# pam-control-module-v0.net
KiCad netlist of a schematic drawn in EAGLE
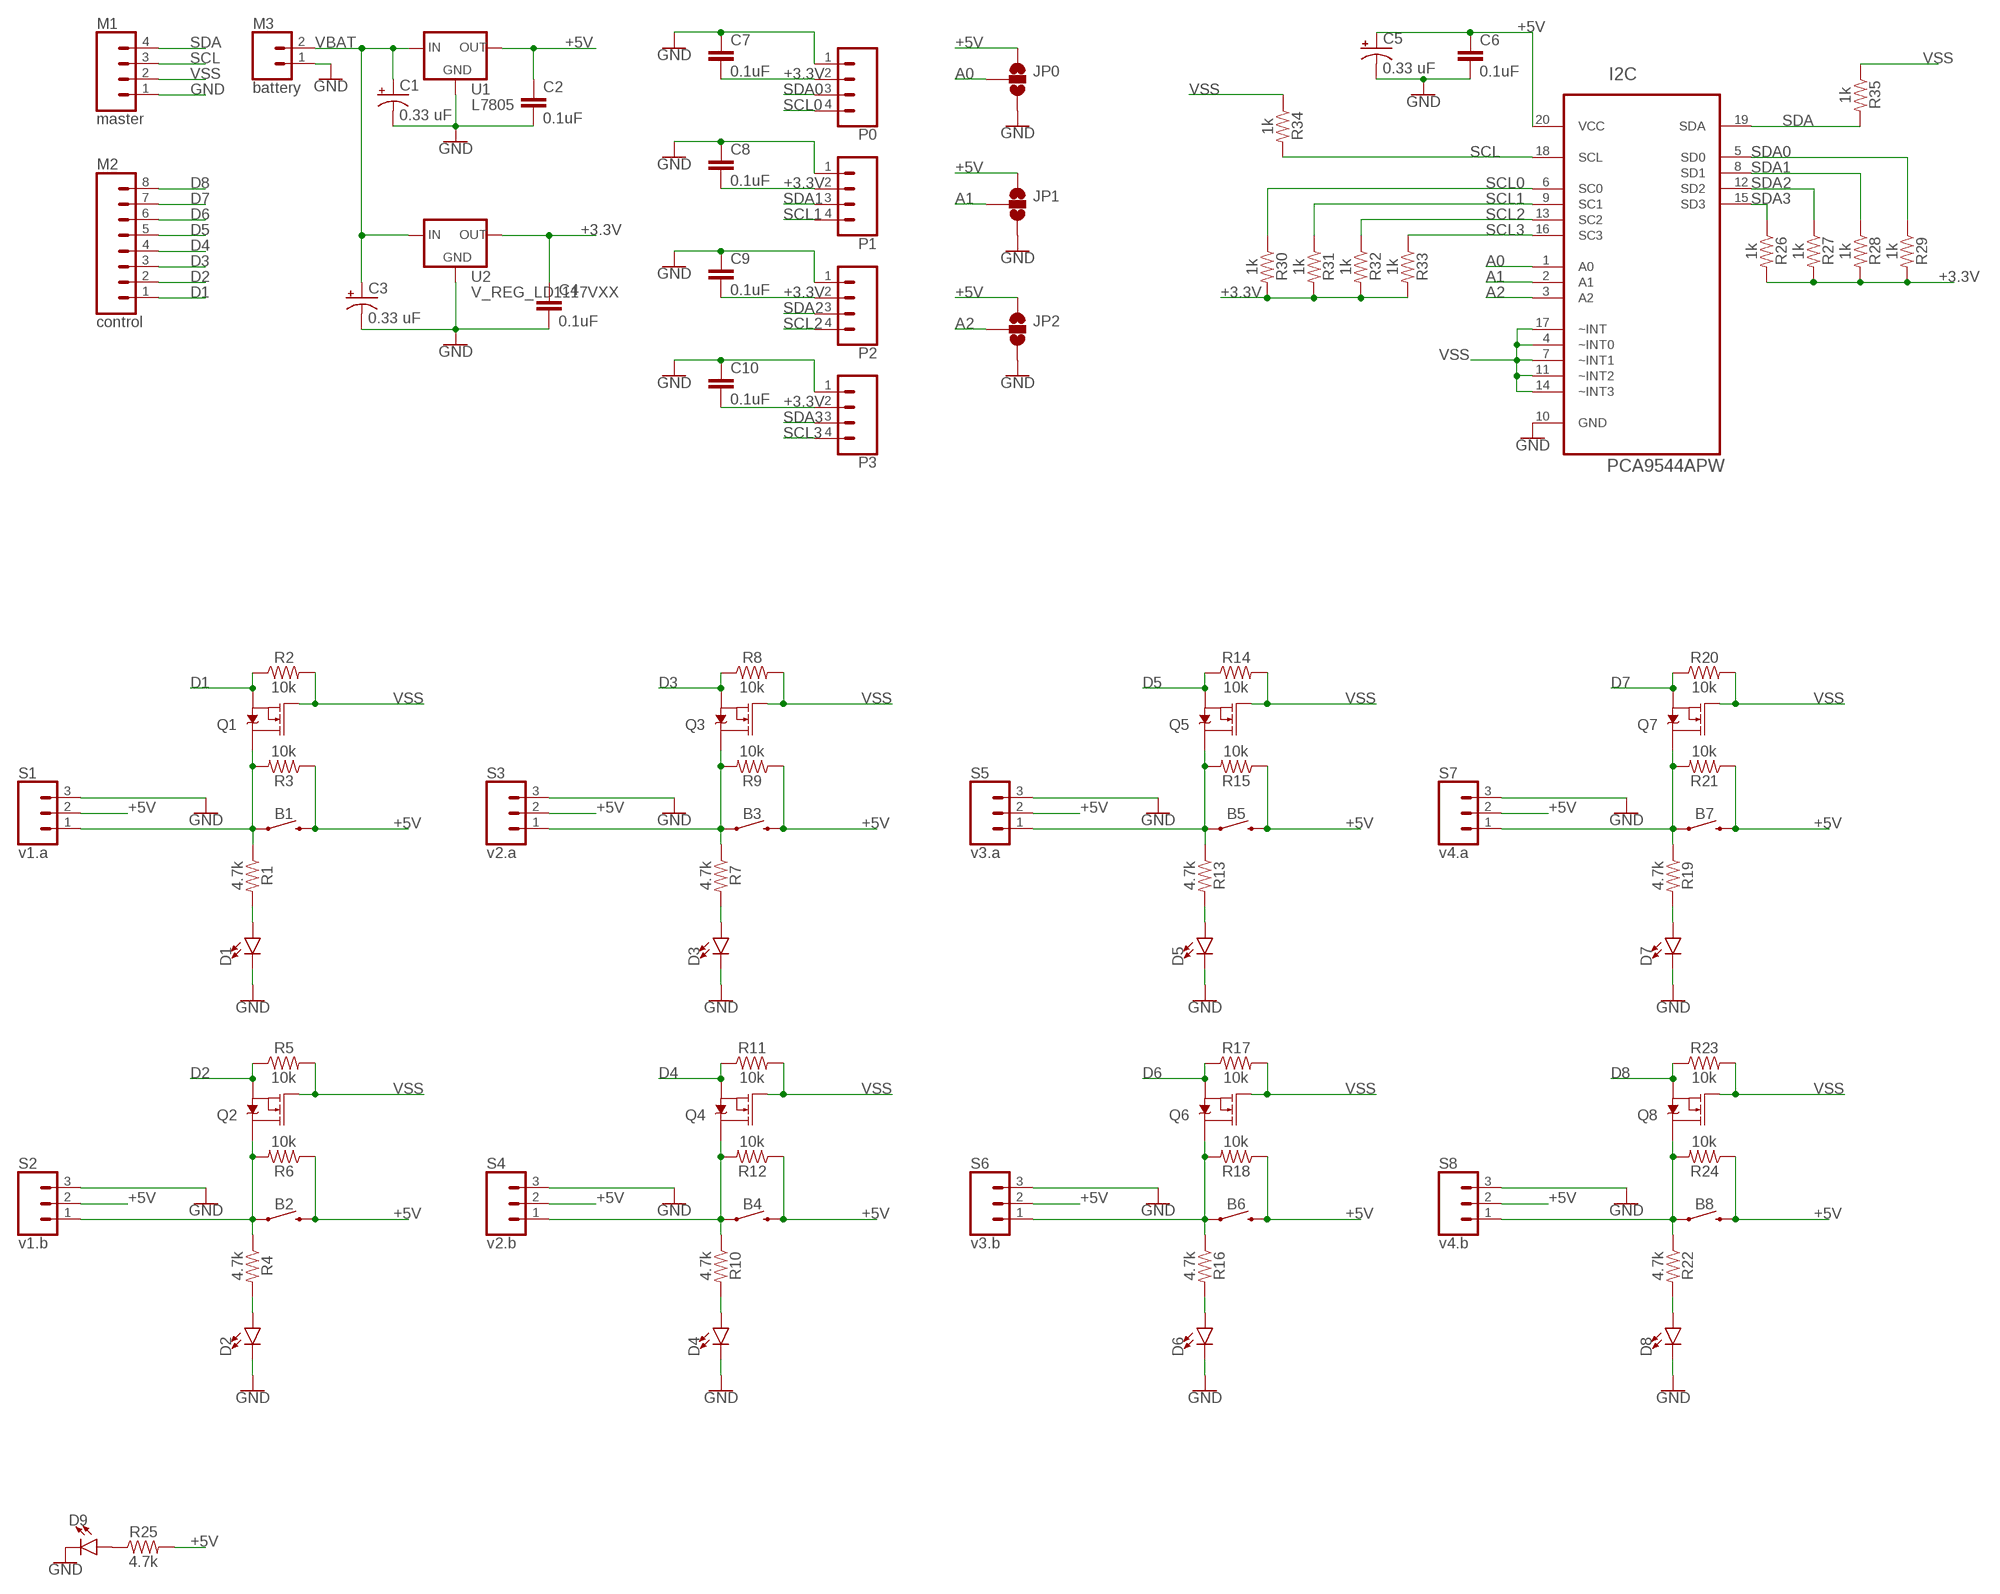
[diagram p0: schematic, sheet 1]

(export (version "E")
  (design (tool "Eeschema 10.0.6"))
  (components
    (comp (ref "B1")
      (value "MOMENTARY-SWITCH-SPST-PTH-6.0MM")
      (footprint "eagle-import:TACTILE_SWITCH_PTH_6.0MM")
      (libsource (lib "eagle-import") (part "MOMENTARY-SWITCH-SPST-PTH-6.0MM"))
    )
    (comp (ref "B2")
      (value "MOMENTARY-SWITCH-SPST-PTH-6.0MM")
      (footprint "eagle-import:TACTILE_SWITCH_PTH_6.0MM")
      (libsource (lib "eagle-import") (part "MOMENTARY-SWITCH-SPST-PTH-6.0MM"))
    )
    (comp (ref "B3")
      (value "MOMENTARY-SWITCH-SPST-PTH-6.0MM")
      (footprint "eagle-import:TACTILE_SWITCH_PTH_6.0MM")
      (libsource (lib "eagle-import") (part "MOMENTARY-SWITCH-SPST-PTH-6.0MM"))
    )
    (comp (ref "B4")
      (value "MOMENTARY-SWITCH-SPST-PTH-6.0MM")
      (footprint "eagle-import:TACTILE_SWITCH_PTH_6.0MM")
      (libsource (lib "eagle-import") (part "MOMENTARY-SWITCH-SPST-PTH-6.0MM"))
    )
    (comp (ref "B5")
      (value "MOMENTARY-SWITCH-SPST-PTH-6.0MM")
      (footprint "eagle-import:TACTILE_SWITCH_PTH_6.0MM")
      (libsource (lib "eagle-import") (part "MOMENTARY-SWITCH-SPST-PTH-6.0MM"))
    )
    (comp (ref "B6")
      (value "MOMENTARY-SWITCH-SPST-PTH-6.0MM")
      (footprint "eagle-import:TACTILE_SWITCH_PTH_6.0MM")
      (libsource (lib "eagle-import") (part "MOMENTARY-SWITCH-SPST-PTH-6.0MM"))
    )
    (comp (ref "B7")
      (value "MOMENTARY-SWITCH-SPST-PTH-6.0MM")
      (footprint "eagle-import:TACTILE_SWITCH_PTH_6.0MM")
      (libsource (lib "eagle-import") (part "MOMENTARY-SWITCH-SPST-PTH-6.0MM"))
    )
    (comp (ref "B8")
      (value "MOMENTARY-SWITCH-SPST-PTH-6.0MM")
      (footprint "eagle-import:TACTILE_SWITCH_PTH_6.0MM")
      (libsource (lib "eagle-import") (part "MOMENTARY-SWITCH-SPST-PTH-6.0MM"))
    )
    (comp (ref "C1")
      (value "0.33 uF")
      (footprint "eagle-import:E2-5")
      (libsource (lib "eagle-import") (part "CPOL-USE2-5"))
    )
    (comp (ref "C2")
      (value "0.1uF")
      (footprint "eagle-import:CAP-PTH-SMALL-KIT")
      (libsource (lib "eagle-import") (part "0.1UF-KIT-EZ-50V-20%"))
    )
    (comp (ref "C3")
      (value "0.33 uF")
      (footprint "eagle-import:E2-5")
      (libsource (lib "eagle-import") (part "CPOL-USE2-5"))
    )
    (comp (ref "C4")
      (value "0.1uF")
      (footprint "eagle-import:CAP-PTH-SMALL-KIT")
      (libsource (lib "eagle-import") (part "0.1UF-KIT-EZ-50V-20%"))
    )
    (comp (ref "C5")
      (value "0.33 uF")
      (footprint "eagle-import:E2-5")
      (libsource (lib "eagle-import") (part "CPOL-USE2-5"))
    )
    (comp (ref "C6")
      (value "0.1uF")
      (footprint "eagle-import:CAP-PTH-SMALL-KIT")
      (libsource (lib "eagle-import") (part "0.1UF-KIT-EZ-50V-20%"))
    )
    (comp (ref "C7")
      (value "0.1uF")
      (footprint "eagle-import:CAP-PTH-SMALL-KIT")
      (libsource (lib "eagle-import") (part "0.1UF-KIT-EZ-50V-20%"))
    )
    (comp (ref "C8")
      (value "0.1uF")
      (footprint "eagle-import:CAP-PTH-SMALL-KIT")
      (libsource (lib "eagle-import") (part "0.1UF-KIT-EZ-50V-20%"))
    )
    (comp (ref "C9")
      (value "0.1uF")
      (footprint "eagle-import:CAP-PTH-SMALL-KIT")
      (libsource (lib "eagle-import") (part "0.1UF-KIT-EZ-50V-20%"))
    )
    (comp (ref "C10")
      (value "0.1uF")
      (footprint "eagle-import:CAP-PTH-SMALL-KIT")
      (libsource (lib "eagle-import") (part "0.1UF-KIT-EZ-50V-20%"))
    )
    (comp (ref "D1")
      (value "LED3MM")
      (footprint "eagle-import:LED_3MM")
      (libsource (lib "eagle-import") (part "LED3MM"))
    )
    (comp (ref "D2")
      (value "LED3MM")
      (footprint "eagle-import:LED_3MM")
      (libsource (lib "eagle-import") (part "LED3MM"))
    )
    (comp (ref "D3")
      (value "LED3MM")
      (footprint "eagle-import:LED_3MM")
      (libsource (lib "eagle-import") (part "LED3MM"))
    )
    (comp (ref "D4")
      (value "LED3MM")
      (footprint "eagle-import:LED_3MM")
      (libsource (lib "eagle-import") (part "LED3MM"))
    )
    (comp (ref "D5")
      (value "LED3MM")
      (footprint "eagle-import:LED_3MM")
      (libsource (lib "eagle-import") (part "LED3MM"))
    )
    (comp (ref "D6")
      (value "LED3MM")
      (footprint "eagle-import:LED_3MM")
      (libsource (lib "eagle-import") (part "LED3MM"))
    )
    (comp (ref "D7")
      (value "LED3MM")
      (footprint "eagle-import:LED_3MM")
      (libsource (lib "eagle-import") (part "LED3MM"))
    )
    (comp (ref "D8")
      (value "LED3MM")
      (footprint "eagle-import:LED_3MM")
      (libsource (lib "eagle-import") (part "LED3MM"))
    )
    (comp (ref "D9")
      (value "LED3MM")
      (footprint "eagle-import:LED_3MM")
      (libsource (lib "eagle-import") (part "LED3MM"))
    )
    (comp (ref "I2C")
      (value "PCA9544APW")
      (footprint "eagle-import:SOP65P640X120-20N")
      (fields (field (name "MF") "Texas Instruments"))
      (libsource (lib "eagle-import") (part "PCA9544APW"))
    )
    (comp (ref "JP0")
      (value "JUMPER-SMT_3_NO_SILK")
      (footprint "eagle-import:SMT-JUMPER_3_NO_SILK")
      (libsource (lib "eagle-import") (part "JUMPER-SMT_3_NO_SILK"))
    )
    (comp (ref "JP1")
      (value "JUMPER-SMT_3_NO_SILK")
      (footprint "eagle-import:SMT-JUMPER_3_NO_SILK")
      (libsource (lib "eagle-import") (part "JUMPER-SMT_3_NO_SILK"))
    )
    (comp (ref "JP2")
      (value "JUMPER-SMT_3_NO_SILK")
      (footprint "eagle-import:SMT-JUMPER_3_NO_SILK")
      (libsource (lib "eagle-import") (part "JUMPER-SMT_3_NO_SILK"))
    )
    (comp (ref "M1")
      (value "master")
      (footprint "eagle-import:1X04")
      (libsource (lib "eagle-import") (part "CONN_04"))
    )
    (comp (ref "M2")
      (value "control")
      (footprint "eagle-import:1X08")
      (libsource (lib "eagle-import") (part "CONN_08{dblquote}"))
    )
    (comp (ref "M3")
      (value "battery")
      (footprint "eagle-import:1X02")
      (libsource (lib "eagle-import") (part "CONN_02"))
    )
    (comp (ref "P0")
      (value "CONN_04")
      (footprint "eagle-import:1X04")
      (libsource (lib "eagle-import") (part "CONN_04"))
    )
    (comp (ref "P1")
      (value "CONN_04")
      (footprint "eagle-import:1X04")
      (libsource (lib "eagle-import") (part "CONN_04"))
    )
    (comp (ref "P2")
      (value "CONN_04")
      (footprint "eagle-import:1X04")
      (libsource (lib "eagle-import") (part "CONN_04"))
    )
    (comp (ref "P3")
      (value "CONN_04")
      (footprint "eagle-import:1X04")
      (libsource (lib "eagle-import") (part "CONN_04"))
    )
    (comp (ref "Q1")
      (value "MOSFET-NCH-BSS138")
      (footprint "eagle-import:SOT23-3")
      (libsource (lib "eagle-import") (part "MOSFET-NCH-BSS138"))
    )
    (comp (ref "Q2")
      (value "MOSFET-NCH-BSS138")
      (footprint "eagle-import:SOT23-3")
      (libsource (lib "eagle-import") (part "MOSFET-NCH-BSS138"))
    )
    (comp (ref "Q3")
      (value "MOSFET-NCH-BSS138")
      (footprint "eagle-import:SOT23-3")
      (libsource (lib "eagle-import") (part "MOSFET-NCH-BSS138"))
    )
    (comp (ref "Q4")
      (value "MOSFET-NCH-BSS138")
      (footprint "eagle-import:SOT23-3")
      (libsource (lib "eagle-import") (part "MOSFET-NCH-BSS138"))
    )
    (comp (ref "Q5")
      (value "MOSFET-NCH-BSS138")
      (footprint "eagle-import:SOT23-3")
      (libsource (lib "eagle-import") (part "MOSFET-NCH-BSS138"))
    )
    (comp (ref "Q6")
      (value "MOSFET-NCH-BSS138")
      (footprint "eagle-import:SOT23-3")
      (libsource (lib "eagle-import") (part "MOSFET-NCH-BSS138"))
    )
    (comp (ref "Q7")
      (value "MOSFET-NCH-BSS138")
      (footprint "eagle-import:SOT23-3")
      (libsource (lib "eagle-import") (part "MOSFET-NCH-BSS138"))
    )
    (comp (ref "Q8")
      (value "MOSFET-NCH-BSS138")
      (footprint "eagle-import:SOT23-3")
      (libsource (lib "eagle-import") (part "MOSFET-NCH-BSS138"))
    )
    (comp (ref "R1")
      (value "4.7k")
      (footprint "eagle-import:AXIAL-0.3")
      (libsource (lib "eagle-import") (part "1KOHM-HORIZ-1/4W-1%"))
    )
    (comp (ref "R2")
      (value "10k")
      (footprint "eagle-import:AXIAL-0.3")
      (libsource (lib "eagle-import") (part "1KOHM-HORIZ-1/4W-1%"))
    )
    (comp (ref "R3")
      (value "10k")
      (footprint "eagle-import:AXIAL-0.3")
      (libsource (lib "eagle-import") (part "1KOHM-HORIZ-1/4W-1%"))
    )
    (comp (ref "R4")
      (value "4.7k")
      (footprint "eagle-import:AXIAL-0.3")
      (libsource (lib "eagle-import") (part "1KOHM-HORIZ-1/4W-1%"))
    )
    (comp (ref "R5")
      (value "10k")
      (footprint "eagle-import:AXIAL-0.3")
      (libsource (lib "eagle-import") (part "1KOHM-HORIZ-1/4W-1%"))
    )
    (comp (ref "R6")
      (value "10k")
      (footprint "eagle-import:AXIAL-0.3")
      (libsource (lib "eagle-import") (part "1KOHM-HORIZ-1/4W-1%"))
    )
    (comp (ref "R7")
      (value "4.7k")
      (footprint "eagle-import:AXIAL-0.3")
      (libsource (lib "eagle-import") (part "1KOHM-HORIZ-1/4W-1%"))
    )
    (comp (ref "R8")
      (value "10k")
      (footprint "eagle-import:AXIAL-0.3")
      (libsource (lib "eagle-import") (part "1KOHM-HORIZ-1/4W-1%"))
    )
    (comp (ref "R9")
      (value "10k")
      (footprint "eagle-import:AXIAL-0.3")
      (libsource (lib "eagle-import") (part "1KOHM-HORIZ-1/4W-1%"))
    )
    (comp (ref "R10")
      (value "4.7k")
      (footprint "eagle-import:AXIAL-0.3")
      (libsource (lib "eagle-import") (part "1KOHM-HORIZ-1/4W-1%"))
    )
    (comp (ref "R11")
      (value "10k")
      (footprint "eagle-import:AXIAL-0.3")
      (libsource (lib "eagle-import") (part "1KOHM-HORIZ-1/4W-1%"))
    )
    (comp (ref "R12")
      (value "10k")
      (footprint "eagle-import:AXIAL-0.3")
      (libsource (lib "eagle-import") (part "1KOHM-HORIZ-1/4W-1%"))
    )
    (comp (ref "R13")
      (value "4.7k")
      (footprint "eagle-import:AXIAL-0.3")
      (libsource (lib "eagle-import") (part "1KOHM-HORIZ-1/4W-1%"))
    )
    (comp (ref "R14")
      (value "10k")
      (footprint "eagle-import:AXIAL-0.3")
      (libsource (lib "eagle-import") (part "1KOHM-HORIZ-1/4W-1%"))
    )
    (comp (ref "R15")
      (value "10k")
      (footprint "eagle-import:AXIAL-0.3")
      (libsource (lib "eagle-import") (part "1KOHM-HORIZ-1/4W-1%"))
    )
    (comp (ref "R16")
      (value "4.7k")
      (footprint "eagle-import:AXIAL-0.3")
      (libsource (lib "eagle-import") (part "1KOHM-HORIZ-1/4W-1%"))
    )
    (comp (ref "R17")
      (value "10k")
      (footprint "eagle-import:AXIAL-0.3")
      (libsource (lib "eagle-import") (part "1KOHM-HORIZ-1/4W-1%"))
    )
    (comp (ref "R18")
      (value "10k")
      (footprint "eagle-import:AXIAL-0.3")
      (libsource (lib "eagle-import") (part "1KOHM-HORIZ-1/4W-1%"))
    )
    (comp (ref "R19")
      (value "4.7k")
      (footprint "eagle-import:AXIAL-0.3")
      (libsource (lib "eagle-import") (part "1KOHM-HORIZ-1/4W-1%"))
    )
    (comp (ref "R20")
      (value "10k")
      (footprint "eagle-import:AXIAL-0.3")
      (libsource (lib "eagle-import") (part "1KOHM-HORIZ-1/4W-1%"))
    )
    (comp (ref "R21")
      (value "10k")
      (footprint "eagle-import:AXIAL-0.3")
      (libsource (lib "eagle-import") (part "1KOHM-HORIZ-1/4W-1%"))
    )
    (comp (ref "R22")
      (value "4.7k")
      (footprint "eagle-import:AXIAL-0.3")
      (libsource (lib "eagle-import") (part "1KOHM-HORIZ-1/4W-1%"))
    )
    (comp (ref "R23")
      (value "10k")
      (footprint "eagle-import:AXIAL-0.3")
      (libsource (lib "eagle-import") (part "1KOHM-HORIZ-1/4W-1%"))
    )
    (comp (ref "R24")
      (value "10k")
      (footprint "eagle-import:AXIAL-0.3")
      (libsource (lib "eagle-import") (part "1KOHM-HORIZ-1/4W-1%"))
    )
    (comp (ref "R25")
      (value "4.7k")
      (footprint "eagle-import:AXIAL-0.3")
      (libsource (lib "eagle-import") (part "1KOHM-HORIZ-1/4W-1%"))
    )
    (comp (ref "R26")
      (value "1k")
      (footprint "eagle-import:AXIAL-0.3")
      (libsource (lib "eagle-import") (part "1KOHM-HORIZ-1/4W-1%"))
    )
    (comp (ref "R27")
      (value "1k")
      (footprint "eagle-import:AXIAL-0.3")
      (libsource (lib "eagle-import") (part "1KOHM-HORIZ-1/4W-1%"))
    )
    (comp (ref "R28")
      (value "1k")
      (footprint "eagle-import:AXIAL-0.3")
      (libsource (lib "eagle-import") (part "1KOHM-HORIZ-1/4W-1%"))
    )
    (comp (ref "R29")
      (value "1k")
      (footprint "eagle-import:AXIAL-0.3")
      (libsource (lib "eagle-import") (part "1KOHM-HORIZ-1/4W-1%"))
    )
    (comp (ref "R30")
      (value "1k")
      (footprint "eagle-import:AXIAL-0.3")
      (libsource (lib "eagle-import") (part "1KOHM-HORIZ-1/4W-1%"))
    )
    (comp (ref "R31")
      (value "1k")
      (footprint "eagle-import:AXIAL-0.3")
      (libsource (lib "eagle-import") (part "1KOHM-HORIZ-1/4W-1%"))
    )
    (comp (ref "R32")
      (value "1k")
      (footprint "eagle-import:AXIAL-0.3")
      (libsource (lib "eagle-import") (part "1KOHM-HORIZ-1/4W-1%"))
    )
    (comp (ref "R33")
      (value "1k")
      (footprint "eagle-import:AXIAL-0.3")
      (libsource (lib "eagle-import") (part "1KOHM-HORIZ-1/4W-1%"))
    )
    (comp (ref "R34")
      (value "1k")
      (footprint "eagle-import:AXIAL-0.3")
      (libsource (lib "eagle-import") (part "1KOHM-HORIZ-1/4W-1%"))
    )
    (comp (ref "R35")
      (value "1k")
      (footprint "eagle-import:AXIAL-0.3")
      (libsource (lib "eagle-import") (part "1KOHM-HORIZ-1/4W-1%"))
    )
    (comp (ref "S1")
      (value "v1.a")
      (footprint "eagle-import:1X03")
      (libsource (lib "eagle-import") (part "CONN_03"))
    )
    (comp (ref "S2")
      (value "v1.b")
      (footprint "eagle-import:1X03")
      (libsource (lib "eagle-import") (part "CONN_03"))
    )
    (comp (ref "S3")
      (value "v2.a")
      (footprint "eagle-import:1X03")
      (libsource (lib "eagle-import") (part "CONN_03"))
    )
    (comp (ref "S4")
      (value "v2.b")
      (footprint "eagle-import:1X03")
      (libsource (lib "eagle-import") (part "CONN_03"))
    )
    (comp (ref "S5")
      (value "v3.a")
      (footprint "eagle-import:1X03")
      (libsource (lib "eagle-import") (part "CONN_03"))
    )
    (comp (ref "S6")
      (value "v3.b")
      (footprint "eagle-import:1X03")
      (libsource (lib "eagle-import") (part "CONN_03"))
    )
    (comp (ref "S7")
      (value "v4.a")
      (footprint "eagle-import:1X03")
      (libsource (lib "eagle-import") (part "CONN_03"))
    )
    (comp (ref "S8")
      (value "v4.b")
      (footprint "eagle-import:1X03")
      (libsource (lib "eagle-import") (part "CONN_03"))
    )
    (comp (ref "U1")
      (value "L7805")
      (footprint "eagle-import:78XXL")
      (libsource (lib "eagle-import") (part "V_REG_78XXSIDE"))
    )
    (comp (ref "U2")
      (value "V_REG_LD1117VXX")
      (footprint "eagle-import:78XXL")
      (libsource (lib "eagle-import") (part "V_REG_LD1117VXX"))
    )
  )
  (nets
    (net (code "1") (name "/+3.3V") (class "Default")
      (node (ref "C10") (pin "2") (pinfunction "2_2") (pintype "passive"))
      (node (ref "C4") (pin "1") (pinfunction "1_1") (pintype "passive"))
      (node (ref "C7") (pin "2") (pinfunction "2_2") (pintype "passive"))
      (node (ref "C8") (pin "2") (pinfunction "2_2") (pintype "passive"))
      (node (ref "C9") (pin "2") (pinfunction "2_2") (pintype "passive"))
      (node (ref "P0") (pin "2") (pinfunction "2_2") (pintype "passive"))
      (node (ref "P1") (pin "2") (pinfunction "2_2") (pintype "passive"))
      (node (ref "P2") (pin "2") (pinfunction "2_2") (pintype "passive"))
      (node (ref "P3") (pin "2") (pinfunction "2_2") (pintype "passive"))
      (node (ref "R26") (pin "P$2") (pinfunction "2_P$2") (pintype "passive"))
      (node (ref "R27") (pin "P$2") (pinfunction "2_P$2") (pintype "passive"))
      (node (ref "R28") (pin "P$2") (pinfunction "2_P$2") (pintype "passive"))
      (node (ref "R29") (pin "P$2") (pinfunction "2_P$2") (pintype "passive"))
      (node (ref "R30") (pin "P$2") (pinfunction "2_P$2") (pintype "passive"))
      (node (ref "R31") (pin "P$2") (pinfunction "2_P$2") (pintype "passive"))
      (node (ref "R32") (pin "P$2") (pinfunction "2_P$2") (pintype "passive"))
      (node (ref "R33") (pin "P$2") (pinfunction "2_P$2") (pintype "passive"))
      (node (ref "U2") (pin "GND") (pinfunction "OUT_GND") (pintype "passive"))
    )
    (net (code "2") (name "/+5V") (class "Default")
      (node (ref "B1") (pin "3") (pinfunction "2_3") (pintype "passive"))
      (node (ref "B2") (pin "3") (pinfunction "2_3") (pintype "passive"))
      (node (ref "B3") (pin "3") (pinfunction "2_3") (pintype "passive"))
      (node (ref "B4") (pin "3") (pinfunction "2_3") (pintype "passive"))
      (node (ref "B5") (pin "3") (pinfunction "2_3") (pintype "passive"))
      (node (ref "B6") (pin "3") (pinfunction "2_3") (pintype "passive"))
      (node (ref "B7") (pin "3") (pinfunction "2_3") (pintype "passive"))
      (node (ref "B8") (pin "3") (pinfunction "2_3") (pintype "passive"))
      (node (ref "C2") (pin "1") (pinfunction "1_1") (pintype "passive"))
      (node (ref "C5") (pin "+") (pinfunction "+_+") (pintype "passive"))
      (node (ref "C6") (pin "1") (pinfunction "1_1") (pintype "passive"))
      (node (ref "I2C") (pin "20") (pinfunction "VCC_20") (pintype "power_in"))
      (node (ref "JP0") (pin "1") (pinfunction "1_1") (pintype "passive"))
      (node (ref "JP1") (pin "1") (pinfunction "1_1") (pintype "passive"))
      (node (ref "JP2") (pin "1") (pinfunction "1_1") (pintype "passive"))
      (node (ref "R12") (pin "P$1") (pinfunction "1_P$1") (pintype "passive"))
      (node (ref "R15") (pin "P$1") (pinfunction "1_P$1") (pintype "passive"))
      (node (ref "R18") (pin "P$1") (pinfunction "1_P$1") (pintype "passive"))
      (node (ref "R21") (pin "P$1") (pinfunction "1_P$1") (pintype "passive"))
      (node (ref "R24") (pin "P$1") (pinfunction "1_P$1") (pintype "passive"))
      (node (ref "R25") (pin "P$2") (pinfunction "2_P$2") (pintype "passive"))
      (node (ref "R3") (pin "P$1") (pinfunction "1_P$1") (pintype "passive"))
      (node (ref "R6") (pin "P$1") (pinfunction "1_P$1") (pintype "passive"))
      (node (ref "R9") (pin "P$1") (pinfunction "1_P$1") (pintype "passive"))
      (node (ref "S1") (pin "2") (pinfunction "2_2") (pintype "passive"))
      (node (ref "S2") (pin "2") (pinfunction "2_2") (pintype "passive"))
      (node (ref "S3") (pin "2") (pinfunction "2_2") (pintype "passive"))
      (node (ref "S4") (pin "2") (pinfunction "2_2") (pintype "passive"))
      (node (ref "S5") (pin "2") (pinfunction "2_2") (pintype "passive"))
      (node (ref "S6") (pin "2") (pinfunction "2_2") (pintype "passive"))
      (node (ref "S7") (pin "2") (pinfunction "2_2") (pintype "passive"))
      (node (ref "S8") (pin "2") (pinfunction "2_2") (pintype "passive"))
      (node (ref "U1") (pin "OUT") (pinfunction "OUT_OUT") (pintype "passive"))
    )
    (net (code "3") (name "/A0") (class "Default")
      (node (ref "I2C") (pin "1") (pinfunction "A0_1") (pintype "input"))
      (node (ref "JP0") (pin "2") (pinfunction "2_2") (pintype "passive"))
    )
    (net (code "4") (name "/A1") (class "Default")
      (node (ref "I2C") (pin "2") (pinfunction "A1_2") (pintype "input"))
      (node (ref "JP1") (pin "2") (pinfunction "2_2") (pintype "passive"))
    )
    (net (code "5") (name "/A2") (class "Default")
      (node (ref "I2C") (pin "3") (pinfunction "A2_3") (pintype "input"))
      (node (ref "JP2") (pin "2") (pinfunction "2_2") (pintype "passive"))
    )
    (net (code "6") (name "/D1") (class "Default")
      (node (ref "M2") (pin "1") (pinfunction "1_1") (pintype "passive"))
      (node (ref "Q1") (pin "2") (pinfunction "S_2") (pintype "bidirectional"))
      (node (ref "R2") (pin "P$1") (pinfunction "1_P$1") (pintype "passive"))
    )
    (net (code "7") (name "/D2") (class "Default")
      (node (ref "M2") (pin "2") (pinfunction "2_2") (pintype "passive"))
      (node (ref "Q2") (pin "2") (pinfunction "S_2") (pintype "bidirectional"))
      (node (ref "R5") (pin "P$1") (pinfunction "1_P$1") (pintype "passive"))
    )
    (net (code "8") (name "/D3") (class "Default")
      (node (ref "M2") (pin "3") (pinfunction "3_3") (pintype "passive"))
      (node (ref "Q3") (pin "2") (pinfunction "S_2") (pintype "bidirectional"))
      (node (ref "R8") (pin "P$1") (pinfunction "1_P$1") (pintype "passive"))
    )
    (net (code "9") (name "/D4") (class "Default")
      (node (ref "M2") (pin "4") (pinfunction "4_4") (pintype "passive"))
      (node (ref "Q4") (pin "2") (pinfunction "S_2") (pintype "bidirectional"))
      (node (ref "R11") (pin "P$1") (pinfunction "1_P$1") (pintype "passive"))
    )
    (net (code "10") (name "/D5") (class "Default")
      (node (ref "M2") (pin "5") (pinfunction "5_5") (pintype "passive"))
      (node (ref "Q5") (pin "2") (pinfunction "S_2") (pintype "bidirectional"))
      (node (ref "R14") (pin "P$1") (pinfunction "1_P$1") (pintype "passive"))
    )
    (net (code "11") (name "/D6") (class "Default")
      (node (ref "M2") (pin "6") (pinfunction "6_6") (pintype "passive"))
      (node (ref "Q6") (pin "2") (pinfunction "S_2") (pintype "bidirectional"))
      (node (ref "R17") (pin "P$1") (pinfunction "1_P$1") (pintype "passive"))
    )
    (net (code "12") (name "/D7") (class "Default")
      (node (ref "M2") (pin "7") (pinfunction "7_7") (pintype "passive"))
      (node (ref "Q7") (pin "2") (pinfunction "S_2") (pintype "bidirectional"))
      (node (ref "R20") (pin "P$1") (pinfunction "1_P$1") (pintype "passive"))
    )
    (net (code "13") (name "/D8") (class "Default")
      (node (ref "M2") (pin "8") (pinfunction "8_8") (pintype "passive"))
      (node (ref "Q8") (pin "2") (pinfunction "S_2") (pintype "bidirectional"))
      (node (ref "R23") (pin "P$1") (pinfunction "1_P$1") (pintype "passive"))
    )
    (net (code "14") (name "/SCL") (class "Default")
      (node (ref "I2C") (pin "18") (pinfunction "SCL_18") (pintype "bidirectional"))
      (node (ref "M1") (pin "3") (pinfunction "3_3") (pintype "passive"))
      (node (ref "R34") (pin "P$2") (pinfunction "2_P$2") (pintype "passive"))
    )
    (net (code "15") (name "/SCL0") (class "Default")
      (node (ref "I2C") (pin "6") (pinfunction "SC0_6") (pintype "bidirectional"))
      (node (ref "P0") (pin "4") (pinfunction "4_4") (pintype "passive"))
      (node (ref "R30") (pin "P$1") (pinfunction "1_P$1") (pintype "passive"))
    )
    (net (code "16") (name "/SCL1") (class "Default")
      (node (ref "I2C") (pin "9") (pinfunction "SC1_9") (pintype "bidirectional"))
      (node (ref "P1") (pin "4") (pinfunction "4_4") (pintype "passive"))
      (node (ref "R31") (pin "P$1") (pinfunction "1_P$1") (pintype "passive"))
    )
    (net (code "17") (name "/SCL2") (class "Default")
      (node (ref "I2C") (pin "13") (pinfunction "SC2_13") (pintype "bidirectional"))
      (node (ref "P2") (pin "4") (pinfunction "4_4") (pintype "passive"))
      (node (ref "R32") (pin "P$1") (pinfunction "1_P$1") (pintype "passive"))
    )
    (net (code "18") (name "/SCL3") (class "Default")
      (node (ref "I2C") (pin "16") (pinfunction "SC3_16") (pintype "bidirectional"))
      (node (ref "P3") (pin "4") (pinfunction "4_4") (pintype "passive"))
      (node (ref "R33") (pin "P$1") (pinfunction "1_P$1") (pintype "passive"))
    )
    (net (code "19") (name "/SDA") (class "Default")
      (node (ref "I2C") (pin "19") (pinfunction "SDA_19") (pintype "bidirectional"))
      (node (ref "M1") (pin "4") (pinfunction "4_4") (pintype "passive"))
      (node (ref "R35") (pin "P$2") (pinfunction "2_P$2") (pintype "passive"))
    )
    (net (code "20") (name "/SDA0") (class "Default")
      (node (ref "I2C") (pin "5") (pinfunction "SD0_5") (pintype "bidirectional"))
      (node (ref "P0") (pin "3") (pinfunction "3_3") (pintype "passive"))
      (node (ref "R29") (pin "P$1") (pinfunction "1_P$1") (pintype "passive"))
    )
    (net (code "21") (name "/SDA1") (class "Default")
      (node (ref "I2C") (pin "8") (pinfunction "SD1_8") (pintype "bidirectional"))
      (node (ref "P1") (pin "3") (pinfunction "3_3") (pintype "passive"))
      (node (ref "R28") (pin "P$1") (pinfunction "1_P$1") (pintype "passive"))
    )
    (net (code "22") (name "/SDA2") (class "Default")
      (node (ref "I2C") (pin "12") (pinfunction "SD2_12") (pintype "bidirectional"))
      (node (ref "P2") (pin "3") (pinfunction "3_3") (pintype "passive"))
      (node (ref "R27") (pin "P$1") (pinfunction "1_P$1") (pintype "passive"))
    )
    (net (code "23") (name "/SDA3") (class "Default")
      (node (ref "I2C") (pin "15") (pinfunction "SD3_15") (pintype "bidirectional"))
      (node (ref "P3") (pin "3") (pinfunction "3_3") (pintype "passive"))
      (node (ref "R26") (pin "P$1") (pinfunction "1_P$1") (pintype "passive"))
    )
    (net (code "24") (name "/VBAT") (class "Default")
      (node (ref "C1") (pin "+") (pinfunction "+_+") (pintype "passive"))
      (node (ref "C3") (pin "+") (pinfunction "+_+") (pintype "passive"))
      (node (ref "M3") (pin "2") (pinfunction "2_2") (pintype "passive"))
      (node (ref "U1") (pin "IN") (pinfunction "IN_IN") (pintype "input"))
      (node (ref "U2") (pin "OUT") (pinfunction "IN_OUT") (pintype "input"))
    )
    (net (code "25") (name "/VSS") (class "Default")
      (node (ref "I2C") (pin "11") (pinfunction "~{INT2}_11") (pintype "input"))
      (node (ref "I2C") (pin "14") (pinfunction "~{INT3}_14") (pintype "input"))
      (node (ref "I2C") (pin "17") (pinfunction "~{INT}_17") (pintype "input"))
      (node (ref "I2C") (pin "4") (pinfunction "~{INT0}_4") (pintype "input"))
      (node (ref "I2C") (pin "7") (pinfunction "~{INT1}_7") (pintype "input"))
      (node (ref "M1") (pin "2") (pinfunction "2_2") (pintype "passive"))
      (node (ref "Q1") (pin "1") (pinfunction "G_1") (pintype "bidirectional"))
      (node (ref "Q2") (pin "1") (pinfunction "G_1") (pintype "bidirectional"))
      (node (ref "Q3") (pin "1") (pinfunction "G_1") (pintype "bidirectional"))
      (node (ref "Q4") (pin "1") (pinfunction "G_1") (pintype "bidirectional"))
      (node (ref "Q5") (pin "1") (pinfunction "G_1") (pintype "bidirectional"))
      (node (ref "Q6") (pin "1") (pinfunction "G_1") (pintype "bidirectional"))
      (node (ref "Q7") (pin "1") (pinfunction "G_1") (pintype "bidirectional"))
      (node (ref "Q8") (pin "1") (pinfunction "G_1") (pintype "bidirectional"))
      (node (ref "R11") (pin "P$2") (pinfunction "2_P$2") (pintype "passive"))
      (node (ref "R14") (pin "P$2") (pinfunction "2_P$2") (pintype "passive"))
      (node (ref "R17") (pin "P$2") (pinfunction "2_P$2") (pintype "passive"))
      (node (ref "R2") (pin "P$2") (pinfunction "2_P$2") (pintype "passive"))
      (node (ref "R20") (pin "P$2") (pinfunction "2_P$2") (pintype "passive"))
      (node (ref "R23") (pin "P$2") (pinfunction "2_P$2") (pintype "passive"))
      (node (ref "R34") (pin "P$1") (pinfunction "1_P$1") (pintype "passive"))
      (node (ref "R35") (pin "P$1") (pinfunction "1_P$1") (pintype "passive"))
      (node (ref "R5") (pin "P$2") (pinfunction "2_P$2") (pintype "passive"))
      (node (ref "R8") (pin "P$2") (pinfunction "2_P$2") (pintype "passive"))
    )
    (net (code "26") (name "GND") (class "Default")
      (node (ref "C1") (pin "-") (pinfunction "-_-") (pintype "passive"))
      (node (ref "C10") (pin "1") (pinfunction "1_1") (pintype "passive"))
      (node (ref "C2") (pin "2") (pinfunction "2_2") (pintype "passive"))
      (node (ref "C3") (pin "-") (pinfunction "-_-") (pintype "passive"))
      (node (ref "C4") (pin "2") (pinfunction "2_2") (pintype "passive"))
      (node (ref "C5") (pin "-") (pinfunction "-_-") (pintype "passive"))
      (node (ref "C6") (pin "2") (pinfunction "2_2") (pintype "passive"))
      (node (ref "C7") (pin "1") (pinfunction "1_1") (pintype "passive"))
      (node (ref "C8") (pin "1") (pinfunction "1_1") (pintype "passive"))
      (node (ref "C9") (pin "1") (pinfunction "1_1") (pintype "passive"))
      (node (ref "D1") (pin "K") (pinfunction "C_K") (pintype "passive"))
      (node (ref "D2") (pin "K") (pinfunction "C_K") (pintype "passive"))
      (node (ref "D3") (pin "K") (pinfunction "C_K") (pintype "passive"))
      (node (ref "D4") (pin "K") (pinfunction "C_K") (pintype "passive"))
      (node (ref "D5") (pin "K") (pinfunction "C_K") (pintype "passive"))
      (node (ref "D6") (pin "K") (pinfunction "C_K") (pintype "passive"))
      (node (ref "D7") (pin "K") (pinfunction "C_K") (pintype "passive"))
      (node (ref "D8") (pin "K") (pinfunction "C_K") (pintype "passive"))
      (node (ref "D9") (pin "K") (pinfunction "C_K") (pintype "passive"))
      (node (ref "I2C") (pin "10") (pinfunction "GND_10") (pintype "passive"))
      (node (ref "JP0") (pin "3") (pinfunction "3_3") (pintype "passive"))
      (node (ref "JP1") (pin "3") (pinfunction "3_3") (pintype "passive"))
      (node (ref "JP2") (pin "3") (pinfunction "3_3") (pintype "passive"))
      (node (ref "M1") (pin "1") (pinfunction "1_1") (pintype "passive"))
      (node (ref "M3") (pin "1") (pinfunction "1_1") (pintype "passive"))
      (node (ref "P0") (pin "1") (pinfunction "1_1") (pintype "passive"))
      (node (ref "P1") (pin "1") (pinfunction "1_1") (pintype "passive"))
      (node (ref "P2") (pin "1") (pinfunction "1_1") (pintype "passive"))
      (node (ref "P3") (pin "1") (pinfunction "1_1") (pintype "passive"))
      (node (ref "S1") (pin "3") (pinfunction "3_3") (pintype "passive"))
      (node (ref "S2") (pin "3") (pinfunction "3_3") (pintype "passive"))
      (node (ref "S3") (pin "3") (pinfunction "3_3") (pintype "passive"))
      (node (ref "S4") (pin "3") (pinfunction "3_3") (pintype "passive"))
      (node (ref "S5") (pin "3") (pinfunction "3_3") (pintype "passive"))
      (node (ref "S6") (pin "3") (pinfunction "3_3") (pintype "passive"))
      (node (ref "S7") (pin "3") (pinfunction "3_3") (pintype "passive"))
      (node (ref "S8") (pin "3") (pinfunction "3_3") (pintype "passive"))
      (node (ref "U1") (pin "GND") (pinfunction "GND_GND") (pintype "input"))
      (node (ref "U2") (pin "IN") (pinfunction "GND_IN") (pintype "input"))
    )
    (net (code "27") (name "Net-(Q1-D)") (class "Default")
      (node (ref "B1") (pin "1") (pinfunction "1_1") (pintype "passive"))
      (node (ref "Q1") (pin "3") (pinfunction "D_3") (pintype "bidirectional"))
      (node (ref "R1") (pin "P$1") (pinfunction "1_P$1") (pintype "passive"))
      (node (ref "R3") (pin "P$2") (pinfunction "2_P$2") (pintype "passive"))
      (node (ref "S1") (pin "1") (pinfunction "1_1") (pintype "passive"))
    )
    (net (code "28") (name "Net-(Q2-D)") (class "Default")
      (node (ref "B2") (pin "1") (pinfunction "1_1") (pintype "passive"))
      (node (ref "Q2") (pin "3") (pinfunction "D_3") (pintype "bidirectional"))
      (node (ref "R4") (pin "P$1") (pinfunction "1_P$1") (pintype "passive"))
      (node (ref "R6") (pin "P$2") (pinfunction "2_P$2") (pintype "passive"))
      (node (ref "S2") (pin "1") (pinfunction "1_1") (pintype "passive"))
    )
    (net (code "29") (name "Net-(Q3-D)") (class "Default")
      (node (ref "B3") (pin "1") (pinfunction "1_1") (pintype "passive"))
      (node (ref "Q3") (pin "3") (pinfunction "D_3") (pintype "bidirectional"))
      (node (ref "R7") (pin "P$1") (pinfunction "1_P$1") (pintype "passive"))
      (node (ref "R9") (pin "P$2") (pinfunction "2_P$2") (pintype "passive"))
      (node (ref "S3") (pin "1") (pinfunction "1_1") (pintype "passive"))
    )
    (net (code "30") (name "Net-(Q4-D)") (class "Default")
      (node (ref "B4") (pin "1") (pinfunction "1_1") (pintype "passive"))
      (node (ref "Q4") (pin "3") (pinfunction "D_3") (pintype "bidirectional"))
      (node (ref "R10") (pin "P$1") (pinfunction "1_P$1") (pintype "passive"))
      (node (ref "R12") (pin "P$2") (pinfunction "2_P$2") (pintype "passive"))
      (node (ref "S4") (pin "1") (pinfunction "1_1") (pintype "passive"))
    )
    (net (code "31") (name "Net-(Q5-D)") (class "Default")
      (node (ref "B5") (pin "1") (pinfunction "1_1") (pintype "passive"))
      (node (ref "Q5") (pin "3") (pinfunction "D_3") (pintype "bidirectional"))
      (node (ref "R13") (pin "P$1") (pinfunction "1_P$1") (pintype "passive"))
      (node (ref "R15") (pin "P$2") (pinfunction "2_P$2") (pintype "passive"))
      (node (ref "S5") (pin "1") (pinfunction "1_1") (pintype "passive"))
    )
    (net (code "32") (name "Net-(Q6-D)") (class "Default")
      (node (ref "B6") (pin "1") (pinfunction "1_1") (pintype "passive"))
      (node (ref "Q6") (pin "3") (pinfunction "D_3") (pintype "bidirectional"))
      (node (ref "R16") (pin "P$1") (pinfunction "1_P$1") (pintype "passive"))
      (node (ref "R18") (pin "P$2") (pinfunction "2_P$2") (pintype "passive"))
      (node (ref "S6") (pin "1") (pinfunction "1_1") (pintype "passive"))
    )
    (net (code "33") (name "Net-(Q7-D)") (class "Default")
      (node (ref "B7") (pin "1") (pinfunction "1_1") (pintype "passive"))
      (node (ref "Q7") (pin "3") (pinfunction "D_3") (pintype "bidirectional"))
      (node (ref "R19") (pin "P$1") (pinfunction "1_P$1") (pintype "passive"))
      (node (ref "R21") (pin "P$2") (pinfunction "2_P$2") (pintype "passive"))
      (node (ref "S7") (pin "1") (pinfunction "1_1") (pintype "passive"))
    )
    (net (code "34") (name "Net-(Q8-D)") (class "Default")
      (node (ref "B8") (pin "1") (pinfunction "1_1") (pintype "passive"))
      (node (ref "Q8") (pin "3") (pinfunction "D_3") (pintype "bidirectional"))
      (node (ref "R22") (pin "P$1") (pinfunction "1_P$1") (pintype "passive"))
      (node (ref "R24") (pin "P$2") (pinfunction "2_P$2") (pintype "passive"))
      (node (ref "S8") (pin "1") (pinfunction "1_1") (pintype "passive"))
    )
    (net (code "35") (name "Net-(R1-2)") (class "Default")
      (node (ref "D1") (pin "A") (pinfunction "A_A") (pintype "passive"))
      (node (ref "R1") (pin "P$2") (pinfunction "2_P$2") (pintype "passive"))
    )
    (net (code "36") (name "Net-(R4-2)") (class "Default")
      (node (ref "D2") (pin "A") (pinfunction "A_A") (pintype "passive"))
      (node (ref "R4") (pin "P$2") (pinfunction "2_P$2") (pintype "passive"))
    )
    (net (code "37") (name "Net-(R7-2)") (class "Default")
      (node (ref "D3") (pin "A") (pinfunction "A_A") (pintype "passive"))
      (node (ref "R7") (pin "P$2") (pinfunction "2_P$2") (pintype "passive"))
    )
    (net (code "38") (name "Net-(R10-2)") (class "Default")
      (node (ref "D4") (pin "A") (pinfunction "A_A") (pintype "passive"))
      (node (ref "R10") (pin "P$2") (pinfunction "2_P$2") (pintype "passive"))
    )
    (net (code "39") (name "Net-(R13-2)") (class "Default")
      (node (ref "D5") (pin "A") (pinfunction "A_A") (pintype "passive"))
      (node (ref "R13") (pin "P$2") (pinfunction "2_P$2") (pintype "passive"))
    )
    (net (code "40") (name "Net-(R16-2)") (class "Default")
      (node (ref "D6") (pin "A") (pinfunction "A_A") (pintype "passive"))
      (node (ref "R16") (pin "P$2") (pinfunction "2_P$2") (pintype "passive"))
    )
    (net (code "41") (name "Net-(R19-2)") (class "Default")
      (node (ref "D7") (pin "A") (pinfunction "A_A") (pintype "passive"))
      (node (ref "R19") (pin "P$2") (pinfunction "2_P$2") (pintype "passive"))
    )
    (net (code "42") (name "Net-(R22-2)") (class "Default")
      (node (ref "D8") (pin "A") (pinfunction "A_A") (pintype "passive"))
      (node (ref "R22") (pin "P$2") (pinfunction "2_P$2") (pintype "passive"))
    )
    (net (code "43") (name "Net-(R25-1)") (class "Default")
      (node (ref "D9") (pin "A") (pinfunction "A_A") (pintype "passive"))
      (node (ref "R25") (pin "P$1") (pinfunction "1_P$1") (pintype "passive"))
    )
  )
)
